# ledmatrixdrive_schematic.net
KiCad netlist of a schematic drawn in EAGLE
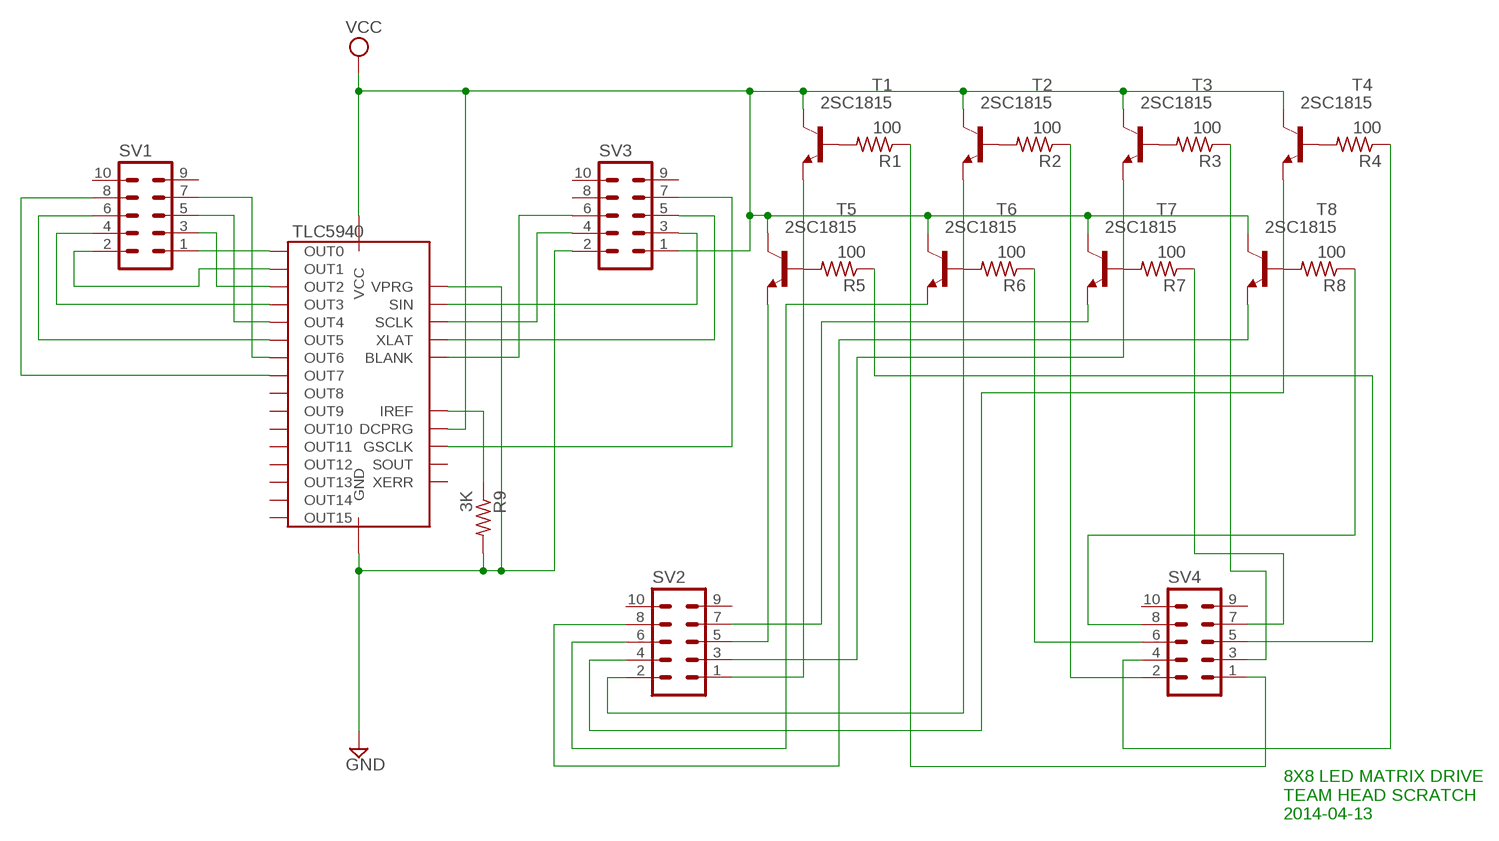
[diagram p0: schematic, sheet 1]

(export (version "E")
  (design (tool "Eeschema 10.0.6"))
  (components
    (comp (ref "R1")
      (value "100")
      (footprint "eagle-import:0204_5")
      (libsource (lib "eagle-import") (part "R-US_0204/5"))
    )
    (comp (ref "R2")
      (value "100")
      (footprint "eagle-import:0204_5")
      (libsource (lib "eagle-import") (part "R-US_0204/5"))
    )
    (comp (ref "R3")
      (value "100")
      (footprint "eagle-import:0204_5")
      (libsource (lib "eagle-import") (part "R-US_0204/5"))
    )
    (comp (ref "R4")
      (value "100")
      (footprint "eagle-import:0204_5")
      (libsource (lib "eagle-import") (part "R-US_0204/5"))
    )
    (comp (ref "R5")
      (value "100")
      (footprint "eagle-import:0204_5")
      (libsource (lib "eagle-import") (part "R-US_0204/5"))
    )
    (comp (ref "R6")
      (value "100")
      (footprint "eagle-import:0204_5")
      (libsource (lib "eagle-import") (part "R-US_0204/5"))
    )
    (comp (ref "R7")
      (value "100")
      (footprint "eagle-import:0204_5")
      (libsource (lib "eagle-import") (part "R-US_0204/5"))
    )
    (comp (ref "R8")
      (value "100")
      (footprint "eagle-import:0204_5")
      (libsource (lib "eagle-import") (part "R-US_0204/5"))
    )
    (comp (ref "R9")
      (value "3K")
      (footprint "eagle-import:0204_5")
      (libsource (lib "eagle-import") (part "R-US_0204/5"))
    )
    (comp (ref "SV1")
      (value "ML10L")
      (footprint "eagle-import:ML10L")
      (libsource (lib "eagle-import") (part "ML10L"))
    )
    (comp (ref "SV2")
      (value "ML10L")
      (footprint "eagle-import:ML10L")
      (libsource (lib "eagle-import") (part "ML10L"))
    )
    (comp (ref "SV3")
      (value "ML10L")
      (footprint "eagle-import:ML10L")
      (libsource (lib "eagle-import") (part "ML10L"))
    )
    (comp (ref "SV4")
      (value "ML10L")
      (footprint "eagle-import:ML10L")
      (libsource (lib "eagle-import") (part "ML10L"))
    )
    (comp (ref "T1")
      (value "2SC1815")
      (footprint "eagle-import:TO92-ECB")
      (libsource (lib "eagle-import") (part "2SC1815"))
    )
    (comp (ref "T2")
      (value "2SC1815")
      (footprint "eagle-import:TO92-ECB")
      (libsource (lib "eagle-import") (part "2SC1815"))
    )
    (comp (ref "T3")
      (value "2SC1815")
      (footprint "eagle-import:TO92-ECB")
      (libsource (lib "eagle-import") (part "2SC1815"))
    )
    (comp (ref "T4")
      (value "2SC1815")
      (footprint "eagle-import:TO92-ECB")
      (libsource (lib "eagle-import") (part "2SC1815"))
    )
    (comp (ref "T5")
      (value "2SC1815")
      (footprint "eagle-import:TO92-ECB")
      (libsource (lib "eagle-import") (part "2SC1815"))
    )
    (comp (ref "T6")
      (value "2SC1815")
      (footprint "eagle-import:TO92-ECB")
      (libsource (lib "eagle-import") (part "2SC1815"))
    )
    (comp (ref "T7")
      (value "2SC1815")
      (footprint "eagle-import:TO92-ECB")
      (libsource (lib "eagle-import") (part "2SC1815"))
    )
    (comp (ref "T8")
      (value "2SC1815")
      (footprint "eagle-import:TO92-ECB")
      (libsource (lib "eagle-import") (part "2SC1815"))
    )
    (comp (ref "TLC5940")
      (value "IC-PACKAGE_DIL28")
      (footprint "eagle-import:IC-PACKAGE_DIL28-6")
      (libsource (lib "eagle-import") (part "IC-PACKAGE_DIL28"))
    )
  )
  (nets
    (net (code "1") (name "GND") (class "Default")
      (node (ref "R9") (pin "2") (pinfunction "2_2") (pintype "passive"))
      (node (ref "SV3") (pin "2") (pinfunction "2_2") (pintype "passive"))
      (node (ref "TLC5940") (pin "22") (pinfunction "GND_22") (pintype "power_in"))
      (node (ref "TLC5940") (pin "27") (pinfunction "VPRG_27") (pintype "input"))
    )
    (net (code "2") (name "Net-(R1-Pad1)") (class "Default")
      (node (ref "R1") (pin "1") (pinfunction "1_1") (pintype "passive"))
      (node (ref "SV4") (pin "1") (pinfunction "1_1") (pintype "passive"))
    )
    (net (code "3") (name "Net-(R1-Pad2)") (class "Default")
      (node (ref "R1") (pin "2") (pinfunction "2_2") (pintype "passive"))
      (node (ref "T1") (pin "B") (pinfunction "B_B") (pintype "passive"))
    )
    (net (code "4") (name "Net-(R2-Pad1)") (class "Default")
      (node (ref "R2") (pin "1") (pinfunction "1_1") (pintype "passive"))
      (node (ref "SV4") (pin "2") (pinfunction "2_2") (pintype "passive"))
    )
    (net (code "5") (name "Net-(R2-Pad2)") (class "Default")
      (node (ref "R2") (pin "2") (pinfunction "2_2") (pintype "passive"))
      (node (ref "T2") (pin "B") (pinfunction "B_B") (pintype "passive"))
    )
    (net (code "6") (name "Net-(R3-Pad1)") (class "Default")
      (node (ref "R3") (pin "1") (pinfunction "1_1") (pintype "passive"))
      (node (ref "SV4") (pin "3") (pinfunction "3_3") (pintype "passive"))
    )
    (net (code "7") (name "Net-(R3-Pad2)") (class "Default")
      (node (ref "R3") (pin "2") (pinfunction "2_2") (pintype "passive"))
      (node (ref "T3") (pin "B") (pinfunction "B_B") (pintype "passive"))
    )
    (net (code "8") (name "Net-(R4-Pad1)") (class "Default")
      (node (ref "R4") (pin "1") (pinfunction "1_1") (pintype "passive"))
      (node (ref "SV4") (pin "4") (pinfunction "4_4") (pintype "passive"))
    )
    (net (code "9") (name "Net-(R4-Pad2)") (class "Default")
      (node (ref "R4") (pin "2") (pinfunction "2_2") (pintype "passive"))
      (node (ref "T4") (pin "B") (pinfunction "B_B") (pintype "passive"))
    )
    (net (code "10") (name "Net-(R5-Pad1)") (class "Default")
      (node (ref "R5") (pin "1") (pinfunction "1_1") (pintype "passive"))
      (node (ref "SV4") (pin "5") (pinfunction "5_5") (pintype "passive"))
    )
    (net (code "11") (name "Net-(R5-Pad2)") (class "Default")
      (node (ref "R5") (pin "2") (pinfunction "2_2") (pintype "passive"))
      (node (ref "T5") (pin "B") (pinfunction "B_B") (pintype "passive"))
    )
    (net (code "12") (name "Net-(R6-Pad1)") (class "Default")
      (node (ref "R6") (pin "1") (pinfunction "1_1") (pintype "passive"))
      (node (ref "SV4") (pin "6") (pinfunction "6_6") (pintype "passive"))
    )
    (net (code "13") (name "Net-(R6-Pad2)") (class "Default")
      (node (ref "R6") (pin "2") (pinfunction "2_2") (pintype "passive"))
      (node (ref "T6") (pin "B") (pinfunction "B_B") (pintype "passive"))
    )
    (net (code "14") (name "Net-(R7-Pad1)") (class "Default")
      (node (ref "R7") (pin "1") (pinfunction "1_1") (pintype "passive"))
      (node (ref "SV4") (pin "7") (pinfunction "7_7") (pintype "passive"))
    )
    (net (code "15") (name "Net-(R7-Pad2)") (class "Default")
      (node (ref "R7") (pin "2") (pinfunction "2_2") (pintype "passive"))
      (node (ref "T7") (pin "B") (pinfunction "B_B") (pintype "passive"))
    )
    (net (code "16") (name "Net-(R8-Pad1)") (class "Default")
      (node (ref "R8") (pin "1") (pinfunction "1_1") (pintype "passive"))
      (node (ref "SV4") (pin "8") (pinfunction "8_8") (pintype "passive"))
    )
    (net (code "17") (name "Net-(R8-Pad2)") (class "Default")
      (node (ref "R8") (pin "2") (pinfunction "2_2") (pintype "passive"))
      (node (ref "T8") (pin "B") (pinfunction "B_B") (pintype "passive"))
    )
    (net (code "18") (name "Net-(SV2-Pad1)") (class "Default")
      (node (ref "SV2") (pin "1") (pinfunction "1_1") (pintype "passive"))
      (node (ref "T1") (pin "E") (pinfunction "E_E") (pintype "passive"))
    )
    (net (code "19") (name "Net-(SV2-Pad2)") (class "Default")
      (node (ref "SV2") (pin "2") (pinfunction "2_2") (pintype "passive"))
      (node (ref "T2") (pin "E") (pinfunction "E_E") (pintype "passive"))
    )
    (net (code "20") (name "Net-(SV2-Pad3)") (class "Default")
      (node (ref "SV2") (pin "3") (pinfunction "3_3") (pintype "passive"))
      (node (ref "T3") (pin "E") (pinfunction "E_E") (pintype "passive"))
    )
    (net (code "21") (name "Net-(SV2-Pad4)") (class "Default")
      (node (ref "SV2") (pin "4") (pinfunction "4_4") (pintype "passive"))
      (node (ref "T4") (pin "E") (pinfunction "E_E") (pintype "passive"))
    )
    (net (code "22") (name "Net-(SV2-Pad5)") (class "Default")
      (node (ref "SV2") (pin "5") (pinfunction "5_5") (pintype "passive"))
      (node (ref "T5") (pin "E") (pinfunction "E_E") (pintype "passive"))
    )
    (net (code "23") (name "Net-(SV2-Pad6)") (class "Default")
      (node (ref "SV2") (pin "6") (pinfunction "6_6") (pintype "passive"))
      (node (ref "T6") (pin "E") (pinfunction "E_E") (pintype "passive"))
    )
    (net (code "24") (name "Net-(SV2-Pad7)") (class "Default")
      (node (ref "SV2") (pin "7") (pinfunction "7_7") (pintype "passive"))
      (node (ref "T7") (pin "E") (pinfunction "E_E") (pintype "passive"))
    )
    (net (code "25") (name "Net-(SV2-Pad8)") (class "Default")
      (node (ref "SV2") (pin "8") (pinfunction "8_8") (pintype "passive"))
      (node (ref "T8") (pin "E") (pinfunction "E_E") (pintype "passive"))
    )
    (net (code "26") (name "Net-(TLC5940-BLANK)") (class "Default")
      (node (ref "SV3") (pin "6") (pinfunction "6_6") (pintype "passive"))
      (node (ref "TLC5940") (pin "23") (pinfunction "BLANK_23") (pintype "input"))
    )
    (net (code "27") (name "Net-(TLC5940-GSCLK)") (class "Default")
      (node (ref "SV3") (pin "7") (pinfunction "7_7") (pintype "passive"))
      (node (ref "TLC5940") (pin "18") (pinfunction "GSCLK_18") (pintype "input"))
    )
    (net (code "28") (name "Net-(TLC5940-IREF)") (class "Default")
      (node (ref "R9") (pin "1") (pinfunction "1_1") (pintype "passive"))
      (node (ref "TLC5940") (pin "20") (pinfunction "IREF_20") (pintype "passive"))
    )
    (net (code "29") (name "Net-(TLC5940-OUT0)") (class "Default")
      (node (ref "SV1") (pin "1") (pinfunction "1_1") (pintype "passive"))
      (node (ref "TLC5940") (pin "28") (pinfunction "OUT0_28") (pintype "open_collector"))
    )
    (net (code "30") (name "Net-(TLC5940-OUT1)") (class "Default")
      (node (ref "SV1") (pin "2") (pinfunction "2_2") (pintype "passive"))
      (node (ref "TLC5940") (pin "1") (pinfunction "OUT1_1") (pintype "open_collector"))
    )
    (net (code "31") (name "Net-(TLC5940-OUT2)") (class "Default")
      (node (ref "SV1") (pin "3") (pinfunction "3_3") (pintype "passive"))
      (node (ref "TLC5940") (pin "2") (pinfunction "OUT2_2") (pintype "open_collector"))
    )
    (net (code "32") (name "Net-(TLC5940-OUT3)") (class "Default")
      (node (ref "SV1") (pin "4") (pinfunction "4_4") (pintype "passive"))
      (node (ref "TLC5940") (pin "3") (pinfunction "OUT3_3") (pintype "open_collector"))
    )
    (net (code "33") (name "Net-(TLC5940-OUT4)") (class "Default")
      (node (ref "SV1") (pin "5") (pinfunction "5_5") (pintype "passive"))
      (node (ref "TLC5940") (pin "4") (pinfunction "OUT4_4") (pintype "open_collector"))
    )
    (net (code "34") (name "Net-(TLC5940-OUT5)") (class "Default")
      (node (ref "SV1") (pin "6") (pinfunction "6_6") (pintype "passive"))
      (node (ref "TLC5940") (pin "5") (pinfunction "OUT5_5") (pintype "open_collector"))
    )
    (net (code "35") (name "Net-(TLC5940-OUT6)") (class "Default")
      (node (ref "SV1") (pin "7") (pinfunction "7_7") (pintype "passive"))
      (node (ref "TLC5940") (pin "6") (pinfunction "OUT6_6") (pintype "open_collector"))
    )
    (net (code "36") (name "Net-(TLC5940-OUT7)") (class "Default")
      (node (ref "SV1") (pin "8") (pinfunction "8_8") (pintype "passive"))
      (node (ref "TLC5940") (pin "7") (pinfunction "OUT7_7") (pintype "open_collector"))
    )
    (net (code "37") (name "Net-(TLC5940-SCLK)") (class "Default")
      (node (ref "SV3") (pin "4") (pinfunction "4_4") (pintype "passive"))
      (node (ref "TLC5940") (pin "25") (pinfunction "SCLK_25") (pintype "input"))
    )
    (net (code "38") (name "Net-(TLC5940-SIN)") (class "Default")
      (node (ref "SV3") (pin "3") (pinfunction "3_3") (pintype "passive"))
      (node (ref "TLC5940") (pin "26") (pinfunction "SIN_26") (pintype "input"))
    )
    (net (code "39") (name "Net-(TLC5940-XLAT)") (class "Default")
      (node (ref "SV3") (pin "5") (pinfunction "5_5") (pintype "passive"))
      (node (ref "TLC5940") (pin "24") (pinfunction "XLAT_24") (pintype "input"))
    )
    (net (code "40") (name "VCC") (class "Default")
      (node (ref "SV3") (pin "1") (pinfunction "1_1") (pintype "passive"))
      (node (ref "T1") (pin "C") (pinfunction "C_C") (pintype "passive"))
      (node (ref "T2") (pin "C") (pinfunction "C_C") (pintype "passive"))
      (node (ref "T3") (pin "C") (pinfunction "C_C") (pintype "passive"))
      (node (ref "T4") (pin "C") (pinfunction "C_C") (pintype "passive"))
      (node (ref "T5") (pin "C") (pinfunction "C_C") (pintype "passive"))
      (node (ref "T6") (pin "C") (pinfunction "C_C") (pintype "passive"))
      (node (ref "T7") (pin "C") (pinfunction "C_C") (pintype "passive"))
      (node (ref "T8") (pin "C") (pinfunction "C_C") (pintype "passive"))
      (node (ref "TLC5940") (pin "19") (pinfunction "DCPRG_19") (pintype "input"))
      (node (ref "TLC5940") (pin "21") (pinfunction "VCC_21") (pintype "power_in"))
    )
    (net (code "41") (name "unconnected-(SV1-Pad9)") (class "Default")
      (node (ref "SV1") (pin "9") (pinfunction "9_9") (pintype "passive"))
    )
    (net (code "42") (name "unconnected-(SV1-Pad10)") (class "Default")
      (node (ref "SV1") (pin "10") (pinfunction "10_10") (pintype "passive"))
    )
    (net (code "43") (name "unconnected-(SV2-Pad9)") (class "Default")
      (node (ref "SV2") (pin "9") (pinfunction "9_9") (pintype "passive"))
    )
    (net (code "44") (name "unconnected-(SV2-Pad10)") (class "Default")
      (node (ref "SV2") (pin "10") (pinfunction "10_10") (pintype "passive"))
    )
    (net (code "45") (name "unconnected-(SV3-Pad8)") (class "Default")
      (node (ref "SV3") (pin "8") (pinfunction "8_8") (pintype "passive"))
    )
    (net (code "46") (name "unconnected-(SV3-Pad9)") (class "Default")
      (node (ref "SV3") (pin "9") (pinfunction "9_9") (pintype "passive"))
    )
    (net (code "47") (name "unconnected-(SV3-Pad10)") (class "Default")
      (node (ref "SV3") (pin "10") (pinfunction "10_10") (pintype "passive"))
    )
    (net (code "48") (name "unconnected-(SV4-Pad9)") (class "Default")
      (node (ref "SV4") (pin "9") (pinfunction "9_9") (pintype "passive"))
    )
    (net (code "49") (name "unconnected-(SV4-Pad10)") (class "Default")
      (node (ref "SV4") (pin "10") (pinfunction "10_10") (pintype "passive"))
    )
    (net (code "50") (name "unconnected-(TLC5940-OUT8-Pad8)") (class "Default")
      (node (ref "TLC5940") (pin "8") (pinfunction "OUT8_8") (pintype "open_collector"))
    )
    (net (code "51") (name "unconnected-(TLC5940-OUT9-Pad9)") (class "Default")
      (node (ref "TLC5940") (pin "9") (pinfunction "OUT9_9") (pintype "open_collector"))
    )
    (net (code "52") (name "unconnected-(TLC5940-OUT10-Pad10)") (class "Default")
      (node (ref "TLC5940") (pin "10") (pinfunction "OUT10_10") (pintype "open_collector"))
    )
    (net (code "53") (name "unconnected-(TLC5940-OUT11-Pad11)") (class "Default")
      (node (ref "TLC5940") (pin "11") (pinfunction "OUT11_11") (pintype "open_collector"))
    )
    (net (code "54") (name "unconnected-(TLC5940-OUT12-Pad12)") (class "Default")
      (node (ref "TLC5940") (pin "12") (pinfunction "OUT12_12") (pintype "open_collector"))
    )
    (net (code "55") (name "unconnected-(TLC5940-OUT13-Pad13)") (class "Default")
      (node (ref "TLC5940") (pin "13") (pinfunction "OUT13_13") (pintype "open_collector"))
    )
    (net (code "56") (name "unconnected-(TLC5940-OUT14-Pad14)") (class "Default")
      (node (ref "TLC5940") (pin "14") (pinfunction "OUT14_14") (pintype "open_collector"))
    )
    (net (code "57") (name "unconnected-(TLC5940-OUT15-Pad15)") (class "Default")
      (node (ref "TLC5940") (pin "15") (pinfunction "OUT15_15") (pintype "open_collector"))
    )
    (net (code "58") (name "unconnected-(TLC5940-SOUT-Pad17)") (class "Default")
      (node (ref "TLC5940") (pin "17") (pinfunction "SOUT_17") (pintype "output"))
    )
    (net (code "59") (name "unconnected-(TLC5940-XERR-Pad16)") (class "Default")
      (node (ref "TLC5940") (pin "16") (pinfunction "XERR_16") (pintype "open_collector"))
    )
  )
)
